# HTparametros.net
KiCad netlist of a schematic drawn in Altium Designer
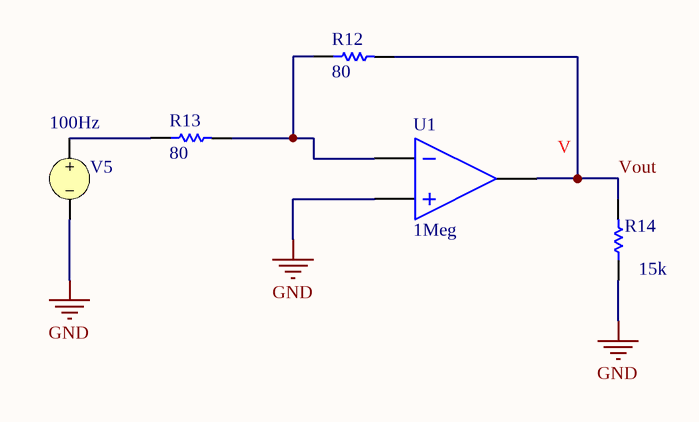
[diagram p0: HTparametros.SchDoc]

(export (version "E")
  (design (tool "Eeschema 10.0.6"))
  (components
    (comp (ref "R12")
      (value "80")
      (description "Resistor")
      (libsource (lib "Simulation Generic Components") (part "Resistor"))
    )
    (comp (ref "R13")
      (value "80")
      (description "Resistor")
      (libsource (lib "Simulation Generic Components") (part "Resistor"))
    )
    (comp (ref "R14")
      (value "15k")
      (description "Resistor")
      (libsource (lib "Simulation Generic Components") (part "Resistor"))
    )
    (comp (ref "U1")
      (value "Ideal Operational Amplifier")
      (fields (field (name "GAIN") "1Meg"))
      (libsource (lib "Simulation Generic Components") (part "OpAmp"))
    )
    (comp (ref "V5")
      (value "SIN(0 1 100Hz 0 0 0)")
      (description "Voltage Source")
      (fields (field (name "FREQUENCY") "100Hz") (field (name "PUBLISHER") "Altium Limited"))
      (libsource (lib "Simulation Generic Components") (part "VSRC"))
    )
  )
  (nets
    (net (code "1") (name "/Vout") (class "Default")
      (node (ref "R12") (pin "2") (pinfunction "2_2") (pintype "passive"))
      (node (ref "R14") (pin "2") (pinfunction "2_2") (pintype "passive"))
      (node (ref "U1") (pin "3") (pinfunction "OUT_3") (pintype "passive"))
    )
    (net (code "2") (name "GND") (class "Default")
      (node (ref "R14") (pin "1") (pinfunction "1_1") (pintype "passive"))
      (node (ref "U1") (pin "2") (pinfunction "IN+_2") (pintype "passive"))
      (node (ref "V5") (pin "2") (pinfunction "2_2") (pintype "passive"))
    )
    (net (code "3") (name "Net-(R13-Pad1)") (class "Default")
      (node (ref "R13") (pin "1") (pinfunction "1_1") (pintype "passive"))
      (node (ref "V5") (pin "1") (pinfunction "1_1") (pintype "passive"))
    )
    (net (code "4") (name "Net-(U1-IN-)") (class "Default")
      (node (ref "R12") (pin "1") (pinfunction "1_1") (pintype "passive"))
      (node (ref "R13") (pin "2") (pinfunction "2_2") (pintype "passive"))
      (node (ref "U1") (pin "1") (pinfunction "IN-_1") (pintype "passive"))
    )
  )
)
